# BOOSTXL-BATPAKMKII.net
KiCad netlist of a schematic drawn in EAGLE
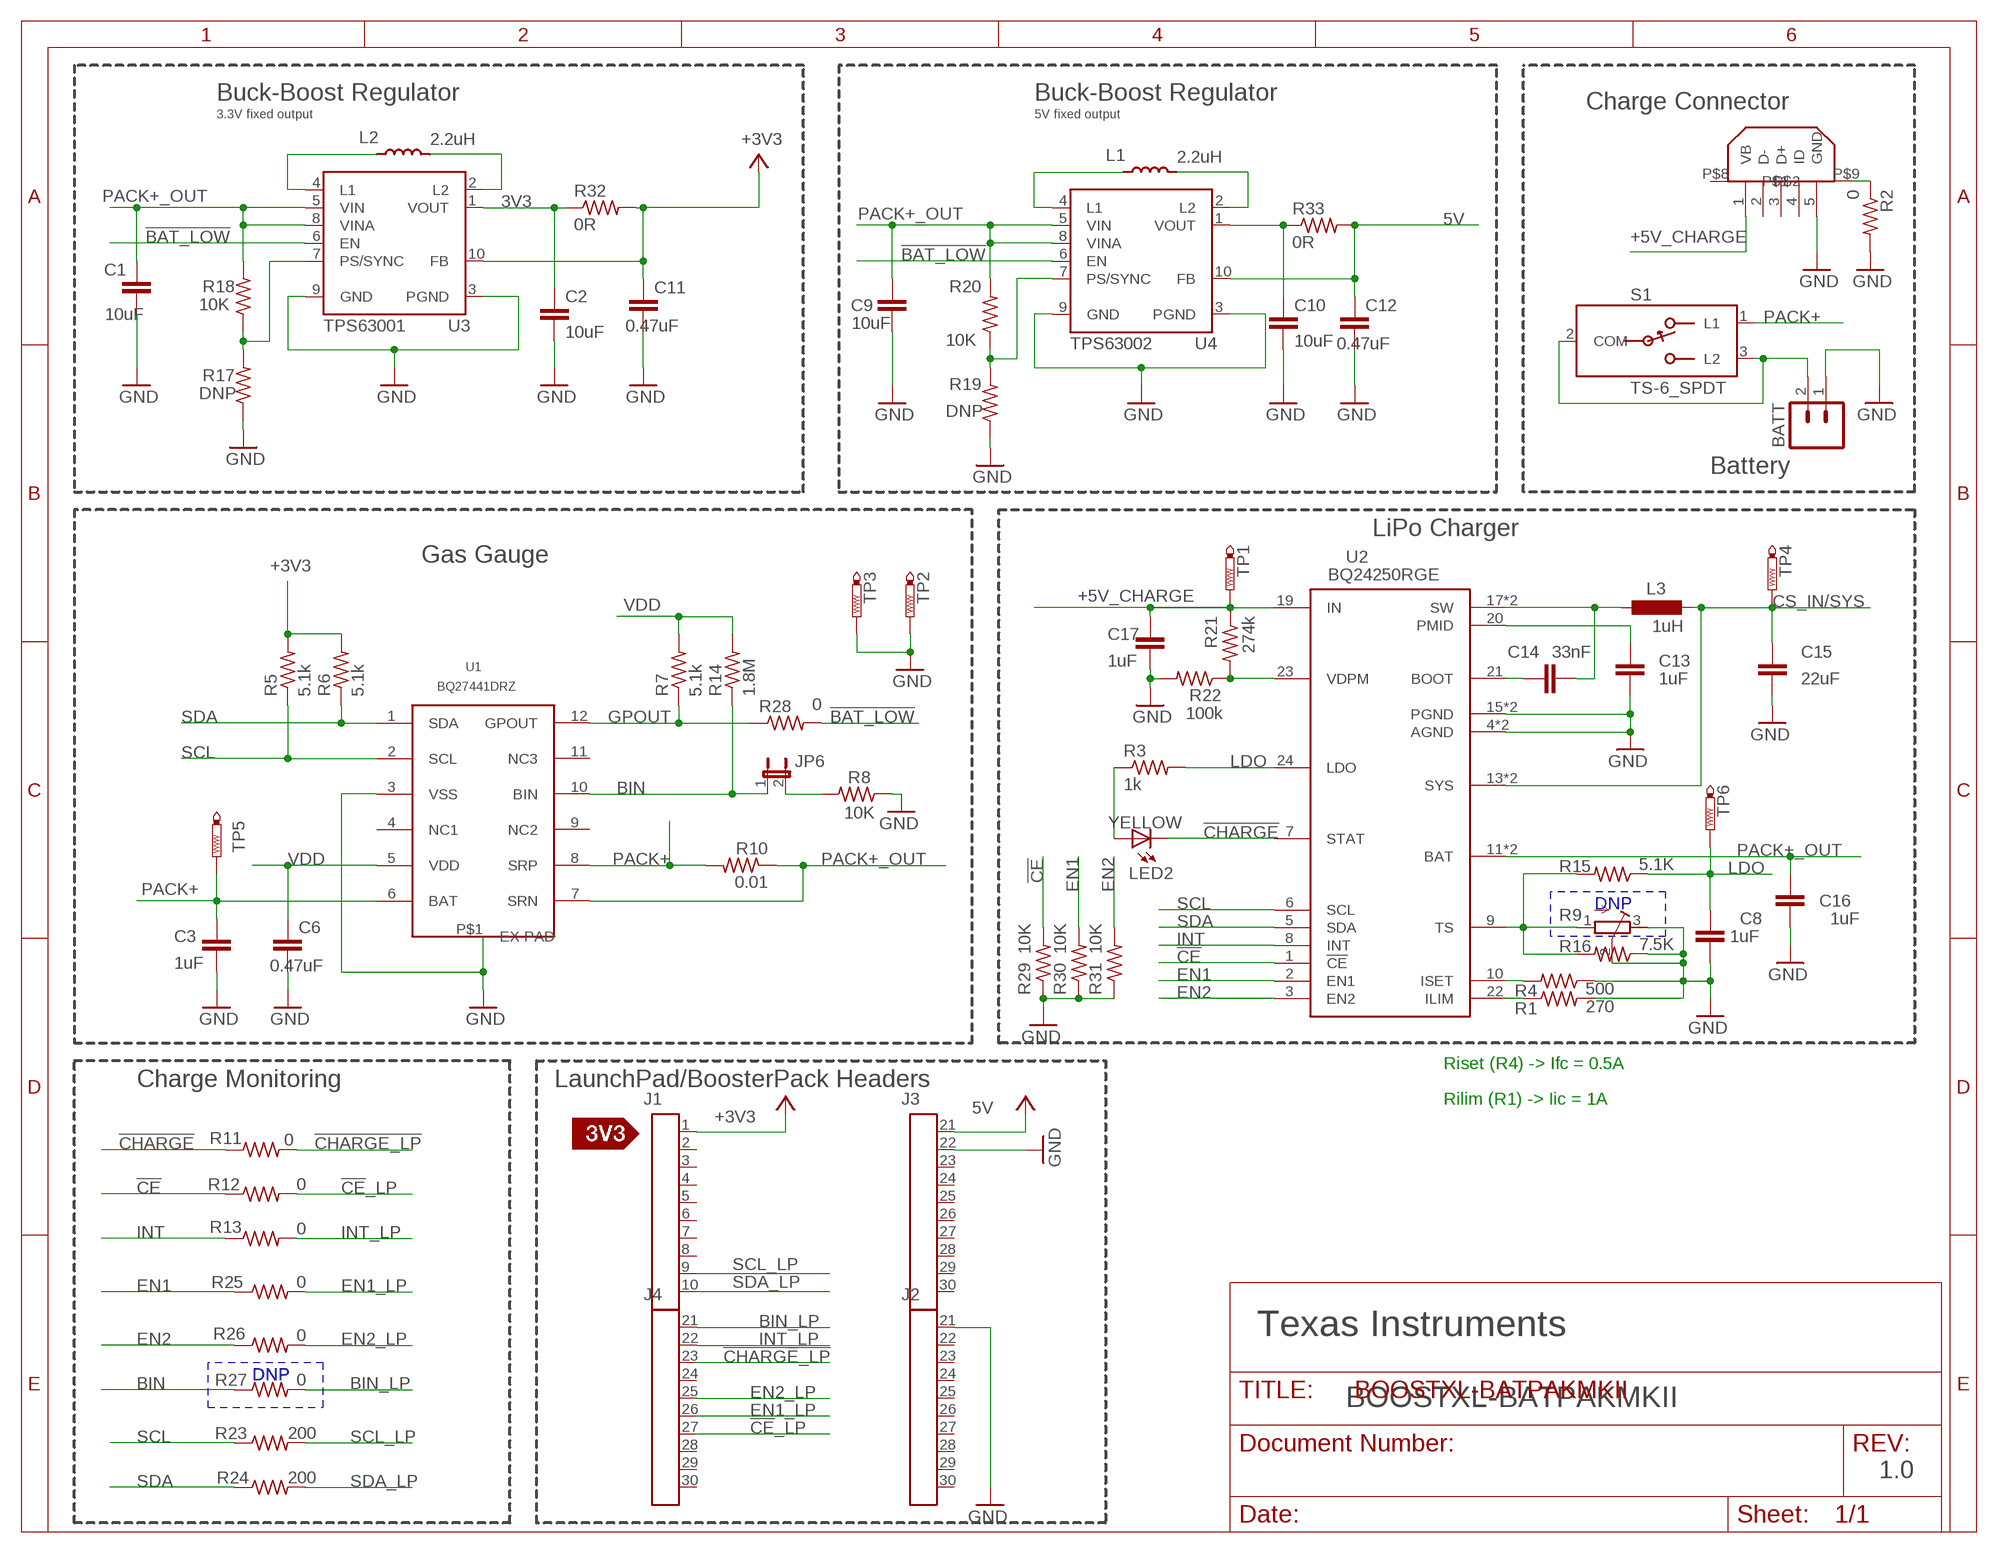
[diagram p0: schematic, sheet 1]

(export (version "E")
  (design (tool "Eeschema 10.0.6"))
  (components
    (comp (ref "BATT")
      (value "M02-JST-2MM-SMT")
      (footprint "eagle-import:JST-2-SMD")
      (libsource (lib "eagle-import") (part "M02-JST-2MM-SMT"))
    )
    (comp (ref "C1")
      (value "10uF")
      (footprint "eagle-import:C0603")
      (libsource (lib "eagle-import") (part "C-EUC0603"))
    )
    (comp (ref "C2")
      (value "10uF")
      (footprint "eagle-import:C0603")
      (libsource (lib "eagle-import") (part "C-EUC0603"))
    )
    (comp (ref "C3")
      (value "1uF")
      (footprint "eagle-import:C0603")
      (libsource (lib "eagle-import") (part "C-EUC0603"))
    )
    (comp (ref "C6")
      (value "0.47uF")
      (footprint "eagle-import:C0603")
      (libsource (lib "eagle-import") (part "C-EUC0603"))
    )
    (comp (ref "C8")
      (value "1uF")
      (footprint "eagle-import:C0603")
      (libsource (lib "eagle-import") (part "C-EUC0603"))
    )
    (comp (ref "C9")
      (value "10uF")
      (footprint "eagle-import:C0603")
      (libsource (lib "eagle-import") (part "C-EUC0603"))
    )
    (comp (ref "C10")
      (value "10uF")
      (footprint "eagle-import:C0603")
      (libsource (lib "eagle-import") (part "C-EUC0603"))
    )
    (comp (ref "C11")
      (value "0.47uF")
      (footprint "eagle-import:C0603")
      (libsource (lib "eagle-import") (part "C-EUC0603"))
    )
    (comp (ref "C12")
      (value "0.47uF")
      (footprint "eagle-import:C0603")
      (libsource (lib "eagle-import") (part "C-EUC0603"))
    )
    (comp (ref "C13")
      (value "1uF")
      (footprint "eagle-import:C0603")
      (libsource (lib "eagle-import") (part "C-EUC0603"))
    )
    (comp (ref "C14")
      (value "33nF")
      (footprint "eagle-import:C0603")
      (libsource (lib "eagle-import") (part "C-EUC0603"))
    )
    (comp (ref "C15")
      (value "22uF")
      (footprint "eagle-import:C0603")
      (libsource (lib "eagle-import") (part "C-EUC0603"))
    )
    (comp (ref "C16")
      (value "1uF")
      (footprint "eagle-import:C0603")
      (libsource (lib "eagle-import") (part "C-EUC0603"))
    )
    (comp (ref "C17")
      (value "1uF")
      (footprint "eagle-import:C0603")
      (libsource (lib "eagle-import") (part "C-EUC0603"))
    )
    (comp (ref "J1")
      (value "HEADER1X10")
      (footprint "eagle-import:1X10")
      (libsource (lib "eagle-import") (part "HEADER1X10"))
    )
    (comp (ref "J2")
      (value "HEADER1X10-J3")
      (footprint "eagle-import:1X10-J3")
      (libsource (lib "eagle-import") (part "HEADER1X10-J3"))
    )
    (comp (ref "J3")
      (value "HEADER1X10-J3")
      (footprint "eagle-import:1X10-J3")
      (libsource (lib "eagle-import") (part "HEADER1X10-J3"))
    )
    (comp (ref "J4")
      (value "HEADER1X10-J3")
      (footprint "eagle-import:1X10-J3")
      (libsource (lib "eagle-import") (part "HEADER1X10-J3"))
    )
    (comp (ref "JP6")
      (value "JP1E")
      (footprint "eagle-import:JP1")
      (libsource (lib "eagle-import") (part "JP1E"))
    )
    (comp (ref "L1")
      (value "2.2uH")
      (footprint "eagle-import:VLF4102A")
      (libsource (lib "eagle-import") (part "VLF4012A"))
    )
    (comp (ref "L2")
      (value "2.2uH")
      (footprint "eagle-import:VLF4102A")
      (libsource (lib "eagle-import") (part "VLF4012A"))
    )
    (comp (ref "L3")
      (value "1uH")
      (footprint "eagle-import:L3216C")
      (libsource (lib "eagle-import") (part "L-EUL3216C"))
    )
    (comp (ref "LED2")
      (value "YELLOW")
      (footprint "eagle-import:RIGHTANGLE_1208")
      (libsource (lib "eagle-import") (part "LED_1208"))
    )
    (comp (ref "R1")
      (value "270")
      (footprint "eagle-import:R0603")
      (libsource (lib "eagle-import") (part "R-US_R0603"))
    )
    (comp (ref "R2")
      (value "0")
      (footprint "eagle-import:R0603")
      (libsource (lib "eagle-import") (part "R-US_R0603"))
    )
    (comp (ref "R3")
      (value "1k")
      (footprint "eagle-import:R0603")
      (libsource (lib "eagle-import") (part "R-US_R0603"))
    )
    (comp (ref "R4")
      (value "500")
      (footprint "eagle-import:R0603")
      (libsource (lib "eagle-import") (part "R-US_R0603"))
    )
    (comp (ref "R5")
      (value "5.1k")
      (footprint "eagle-import:R0603")
      (libsource (lib "eagle-import") (part "R-US_R0603"))
    )
    (comp (ref "R6")
      (value "5.1k")
      (footprint "eagle-import:R0603")
      (libsource (lib "eagle-import") (part "R-US_R0603"))
    )
    (comp (ref "R7")
      (value "5.1k")
      (footprint "eagle-import:R0603")
      (libsource (lib "eagle-import") (part "R-US_R0603"))
    )
    (comp (ref "R8")
      (value "10K")
      (footprint "eagle-import:R0603")
      (libsource (lib "eagle-import") (part "R-US_R0603"))
    )
    (comp (ref "R9")
      (value "R-TRIMM3296W")
      (footprint "eagle-import:RTRIM3296W")
      (libsource (lib "eagle-import") (part "R-TRIMM3296W"))
    )
    (comp (ref "R10")
      (value "0.01")
      (footprint "eagle-import:R1206")
      (libsource (lib "eagle-import") (part "R-US_R1206"))
    )
    (comp (ref "R11")
      (value "0")
      (footprint "eagle-import:R0603")
      (libsource (lib "eagle-import") (part "R-US_R0603"))
    )
    (comp (ref "R12")
      (value "0")
      (footprint "eagle-import:R0603")
      (libsource (lib "eagle-import") (part "R-US_R0603"))
    )
    (comp (ref "R13")
      (value "0")
      (footprint "eagle-import:R0603")
      (libsource (lib "eagle-import") (part "R-US_R0603"))
    )
    (comp (ref "R14")
      (value "1.8M")
      (footprint "eagle-import:R0603")
      (libsource (lib "eagle-import") (part "R-US_R0603"))
    )
    (comp (ref "R15")
      (value "5.1K")
      (footprint "eagle-import:R0603")
      (libsource (lib "eagle-import") (part "R-US_R0603"))
    )
    (comp (ref "R16")
      (value "7.5K")
      (footprint "eagle-import:R0603")
      (libsource (lib "eagle-import") (part "R-US_R0603"))
    )
    (comp (ref "R17")
      (value "DNP")
      (footprint "eagle-import:R0603")
      (libsource (lib "eagle-import") (part "R-US_R0603"))
    )
    (comp (ref "R18")
      (value "10K")
      (footprint "eagle-import:R0603")
      (libsource (lib "eagle-import") (part "R-US_R0603"))
    )
    (comp (ref "R19")
      (value "DNP")
      (footprint "eagle-import:R0603")
      (libsource (lib "eagle-import") (part "R-US_R0603"))
    )
    (comp (ref "R20")
      (value "10K")
      (footprint "eagle-import:R0603")
      (libsource (lib "eagle-import") (part "R-US_R0603"))
    )
    (comp (ref "R21")
      (value "274k")
      (footprint "eagle-import:R0603")
      (libsource (lib "eagle-import") (part "R-US_R0603"))
    )
    (comp (ref "R22")
      (value "100k")
      (footprint "eagle-import:R0603")
      (libsource (lib "eagle-import") (part "R-US_R0603"))
    )
    (comp (ref "R23")
      (value "200")
      (footprint "eagle-import:R0603")
      (libsource (lib "eagle-import") (part "R-US_R0603"))
    )
    (comp (ref "R24")
      (value "200")
      (footprint "eagle-import:R0603")
      (libsource (lib "eagle-import") (part "R-US_R0603"))
    )
    (comp (ref "R25")
      (value "0")
      (footprint "eagle-import:R0603")
      (libsource (lib "eagle-import") (part "R-US_R0603"))
    )
    (comp (ref "R26")
      (value "0")
      (footprint "eagle-import:R0603")
      (libsource (lib "eagle-import") (part "R-US_R0603"))
    )
    (comp (ref "R27")
      (value "0")
      (footprint "eagle-import:R0603")
      (libsource (lib "eagle-import") (part "R-US_R0603"))
    )
    (comp (ref "R28")
      (value "0")
      (footprint "eagle-import:R0603")
      (libsource (lib "eagle-import") (part "R-US_R0603"))
    )
    (comp (ref "R29")
      (value "10K")
      (footprint "eagle-import:R0603")
      (libsource (lib "eagle-import") (part "R-US_R0603"))
    )
    (comp (ref "R30")
      (value "10K")
      (footprint "eagle-import:R0603")
      (libsource (lib "eagle-import") (part "R-US_R0603"))
    )
    (comp (ref "R31")
      (value "10K")
      (footprint "eagle-import:R0603")
      (libsource (lib "eagle-import") (part "R-US_R0603"))
    )
    (comp (ref "R32")
      (value "0R")
      (footprint "eagle-import:R0805")
      (libsource (lib "eagle-import") (part "R-US_R0805"))
    )
    (comp (ref "R33")
      (value "0R")
      (footprint "eagle-import:R0805")
      (libsource (lib "eagle-import") (part "R-US_R0805"))
    )
    (comp (ref "S1")
      (value "TS-6_SPDT")
      (footprint "eagle-import:TS-6_SPDT")
      (libsource (lib "eagle-import") (part "TS-6_SPDT"))
    )
    (comp (ref "TP1")
      (value "PTR1PAD1-13")
      (footprint "eagle-import:P1-13")
      (libsource (lib "eagle-import") (part "PTR1PAD1-13"))
    )
    (comp (ref "TP2")
      (value "PTR1PAD1-13")
      (footprint "eagle-import:P1-13")
      (libsource (lib "eagle-import") (part "PTR1PAD1-13"))
    )
    (comp (ref "TP3")
      (value "PTR1PAD1-13")
      (footprint "eagle-import:P1-13")
      (libsource (lib "eagle-import") (part "PTR1PAD1-13"))
    )
    (comp (ref "TP4")
      (value "PTR1PAD1-13")
      (footprint "eagle-import:P1-13")
      (libsource (lib "eagle-import") (part "PTR1PAD1-13"))
    )
    (comp (ref "TP5")
      (value "PTR1PAD1-13")
      (footprint "eagle-import:P1-13")
      (libsource (lib "eagle-import") (part "PTR1PAD1-13"))
    )
    (comp (ref "TP6")
      (value "PTR1PAD1-13")
      (footprint "eagle-import:P1-13")
      (libsource (lib "eagle-import") (part "PTR1PAD1-13"))
    )
    (comp (ref "U$1")
      (value "SILK_3V3_TAG")
      (footprint "eagle-import:SILK_3V3_TAG")
      (libsource (lib "eagle-import") (part "SILK_3V3_TAG"))
    )
    (comp (ref "U$2")
      (value "MS_(TM)")
      (footprint "eagle-import:MS_(TM)")
      (libsource (lib "eagle-import") (part "MS_(TM)"))
    )
    (comp (ref "U1")
      (value "BQ27441DRZ")
      (footprint "eagle-import:DRZ12")
      (libsource (lib "eagle-import") (part "BQ27441DRZ"))
    )
    (comp (ref "U2")
      (value "BQ24250RGE")
      (footprint "eagle-import:TI_RGE24")
      (libsource (lib "eagle-import") (part "BQ24250RGE"))
    )
    (comp (ref "U3")
      (value "TPS63001")
      (footprint "eagle-import:DRC-S-PVSON-N10")
      (fields (field (name "MPN") "TPS63000DRCTG4"))
      (libsource (lib "eagle-import") (part "TPS6300"))
    )
    (comp (ref "U4")
      (value "TPS63002")
      (footprint "eagle-import:DRC-S-PVSON-N10")
      (fields (field (name "MPN") "TPS63000DRCTG4"))
      (libsource (lib "eagle-import") (part "TPS6300"))
    )
    (comp (ref "USB")
      (value "CONN_USB_MICRO_B")
      (footprint "eagle-import:USB_MICRO_B_SMT")
      (libsource (lib "eagle-import") (part "CONN_USB_MICRO_B"))
    )
  )
  (nets
    (net (code "1") (name "+3V3") (class "Default")
      (node (ref "C11") (pin "1") (pinfunction "1_1") (pintype "passive"))
      (node (ref "J1") (pin "1") (pinfunction "1_1") (pintype "bidirectional"))
      (node (ref "R32") (pin "2") (pinfunction "2_2") (pintype "passive"))
      (node (ref "R5") (pin "2") (pinfunction "2_2") (pintype "passive"))
      (node (ref "R6") (pin "2") (pinfunction "2_2") (pintype "passive"))
      (node (ref "U3") (pin "10") (pinfunction "FB_10") (pintype "input"))
    )
    (net (code "2") (name "/+5V_CHARGE") (class "Default")
      (node (ref "C17") (pin "1") (pinfunction "1_1") (pintype "passive"))
      (node (ref "R21") (pin "1") (pinfunction "1_1") (pintype "passive"))
      (node (ref "TP1") (pin "TP") (pinfunction "TP_TP") (pintype "input"))
      (node (ref "U2") (pin "19") (pinfunction "IN_19") (pintype "bidirectional"))
      (node (ref "USB") (pin "1") (pinfunction "VB_1") (pintype "bidirectional"))
    )
    (net (code "3") (name "/3V3") (class "Default")
      (node (ref "C2") (pin "1") (pinfunction "1_1") (pintype "passive"))
      (node (ref "R32") (pin "1") (pinfunction "1_1") (pintype "passive"))
      (node (ref "U3") (pin "1") (pinfunction "VOUT_1") (pintype "output"))
    )
    (net (code "4") (name "/BIN") (class "Default")
      (node (ref "JP6") (pin "1") (pinfunction "1_1") (pintype "passive"))
      (node (ref "R14") (pin "1") (pinfunction "1_1") (pintype "passive"))
      (node (ref "R27") (pin "1") (pinfunction "1_1") (pintype "passive"))
      (node (ref "U1") (pin "10") (pinfunction "BIN_10") (pintype "bidirectional"))
    )
    (net (code "5") (name "/BIN_LP") (class "Default")
      (node (ref "J4") (pin "21") (pinfunction "1_21") (pintype "bidirectional"))
      (node (ref "R27") (pin "2") (pinfunction "2_2") (pintype "passive"))
    )
    (net (code "6") (name "/CS_IN{slash}SYS") (class "Default")
      (node (ref "C15") (pin "1") (pinfunction "1_1") (pintype "passive"))
      (node (ref "L3") (pin "2") (pinfunction "2_2") (pintype "passive"))
      (node (ref "TP4") (pin "TP") (pinfunction "TP_TP") (pintype "input"))
      (node (ref "U2") (pin "13") (pinfunction "SYS_13") (pintype "bidirectional"))
      (node (ref "U2") (pin "14") (pinfunction "SYS_14") (pintype "bidirectional"))
    )
    (net (code "7") (name "/EN1") (class "Default")
      (node (ref "R25") (pin "1") (pinfunction "1_1") (pintype "passive"))
      (node (ref "R30") (pin "2") (pinfunction "2_2") (pintype "passive"))
      (node (ref "U2") (pin "2") (pinfunction "EN1_2") (pintype "bidirectional"))
    )
    (net (code "8") (name "/EN1_LP") (class "Default")
      (node (ref "J4") (pin "26") (pinfunction "6_26") (pintype "bidirectional"))
      (node (ref "R25") (pin "2") (pinfunction "2_2") (pintype "passive"))
    )
    (net (code "9") (name "/EN2") (class "Default")
      (node (ref "R26") (pin "1") (pinfunction "1_1") (pintype "passive"))
      (node (ref "R31") (pin "2") (pinfunction "2_2") (pintype "passive"))
      (node (ref "U2") (pin "3") (pinfunction "EN2_3") (pintype "bidirectional"))
    )
    (net (code "10") (name "/EN2_LP") (class "Default")
      (node (ref "J4") (pin "25") (pinfunction "5_25") (pintype "bidirectional"))
      (node (ref "R26") (pin "2") (pinfunction "2_2") (pintype "passive"))
    )
    (net (code "11") (name "/GPOUT") (class "Default")
      (node (ref "R28") (pin "1") (pinfunction "1_1") (pintype "passive"))
      (node (ref "R7") (pin "1") (pinfunction "1_1") (pintype "passive"))
      (node (ref "U1") (pin "12") (pinfunction "GPOUT_12") (pintype "bidirectional"))
    )
    (net (code "12") (name "/INT") (class "Default")
      (node (ref "R13") (pin "1") (pinfunction "1_1") (pintype "passive"))
      (node (ref "U2") (pin "8") (pinfunction "INT_8") (pintype "bidirectional"))
    )
    (net (code "13") (name "/INT_LP") (class "Default")
      (node (ref "J4") (pin "22") (pinfunction "2_22") (pintype "bidirectional"))
      (node (ref "R13") (pin "2") (pinfunction "2_2") (pintype "passive"))
    )
    (net (code "14") (name "/LDO") (class "Default")
      (node (ref "C8") (pin "1") (pinfunction "1_1") (pintype "passive"))
      (node (ref "R15") (pin "1") (pinfunction "1_1") (pintype "passive"))
      (node (ref "R3") (pin "2") (pinfunction "2_2") (pintype "passive"))
      (node (ref "TP6") (pin "TP") (pinfunction "TP_TP") (pintype "input"))
      (node (ref "U2") (pin "24") (pinfunction "LDO_24") (pintype "bidirectional"))
    )
    (net (code "15") (name "/PACK+") (class "Default")
      (node (ref "C3") (pin "1") (pinfunction "1_1") (pintype "passive"))
      (node (ref "R10") (pin "2") (pinfunction "2_2") (pintype "passive"))
      (node (ref "S1") (pin "1") (pinfunction "L1_1") (pintype "bidirectional"))
      (node (ref "TP5") (pin "TP") (pinfunction "TP_TP") (pintype "input"))
      (node (ref "U1") (pin "6") (pinfunction "BAT_6") (pintype "bidirectional"))
      (node (ref "U1") (pin "8") (pinfunction "SRP_8") (pintype "bidirectional"))
    )
    (net (code "16") (name "/PACK+_OUT") (class "Default")
      (node (ref "C1") (pin "1") (pinfunction "1_1") (pintype "passive"))
      (node (ref "C16") (pin "1") (pinfunction "1_1") (pintype "passive"))
      (node (ref "C9") (pin "1") (pinfunction "1_1") (pintype "passive"))
      (node (ref "R10") (pin "1") (pinfunction "1_1") (pintype "passive"))
      (node (ref "R18") (pin "2") (pinfunction "2_2") (pintype "passive"))
      (node (ref "R20") (pin "2") (pinfunction "2_2") (pintype "passive"))
      (node (ref "U1") (pin "7") (pinfunction "SRN_7") (pintype "bidirectional"))
      (node (ref "U2") (pin "11") (pinfunction "BAT_11") (pintype "bidirectional"))
      (node (ref "U2") (pin "12") (pinfunction "BAT_12") (pintype "bidirectional"))
      (node (ref "U3") (pin "5") (pinfunction "VIN_5") (pintype "input"))
      (node (ref "U3") (pin "8") (pinfunction "VINA_8") (pintype "input"))
      (node (ref "U4") (pin "5") (pinfunction "VIN_5") (pintype "input"))
      (node (ref "U4") (pin "8") (pinfunction "VINA_8") (pintype "input"))
    )
    (net (code "17") (name "/SCL") (class "Default")
      (node (ref "R23") (pin "1") (pinfunction "1_1") (pintype "passive"))
      (node (ref "R5") (pin "1") (pinfunction "1_1") (pintype "passive"))
      (node (ref "U1") (pin "2") (pinfunction "SCL_2") (pintype "bidirectional"))
      (node (ref "U2") (pin "6") (pinfunction "SCL_6") (pintype "bidirectional"))
    )
    (net (code "18") (name "/SCL_LP") (class "Default")
      (node (ref "J1") (pin "9") (pinfunction "9_9") (pintype "bidirectional"))
      (node (ref "R23") (pin "2") (pinfunction "2_2") (pintype "passive"))
    )
    (net (code "19") (name "/SDA") (class "Default")
      (node (ref "R24") (pin "1") (pinfunction "1_1") (pintype "passive"))
      (node (ref "R6") (pin "1") (pinfunction "1_1") (pintype "passive"))
      (node (ref "U1") (pin "1") (pinfunction "SDA_1") (pintype "bidirectional"))
      (node (ref "U2") (pin "5") (pinfunction "SDA_5") (pintype "bidirectional"))
    )
    (net (code "20") (name "/SDA_LP") (class "Default")
      (node (ref "J1") (pin "10") (pinfunction "10_10") (pintype "bidirectional"))
      (node (ref "R24") (pin "2") (pinfunction "2_2") (pintype "passive"))
    )
    (net (code "21") (name "/VDD") (class "Default")
      (node (ref "C6") (pin "1") (pinfunction "1_1") (pintype "passive"))
      (node (ref "R14") (pin "2") (pinfunction "2_2") (pintype "passive"))
      (node (ref "R7") (pin "2") (pinfunction "2_2") (pintype "passive"))
      (node (ref "U1") (pin "5") (pinfunction "VDD_5") (pintype "bidirectional"))
    )
    (net (code "22") (name "/~{BAT_LOW}") (class "Default")
      (node (ref "R28") (pin "2") (pinfunction "2_2") (pintype "passive"))
      (node (ref "U3") (pin "6") (pinfunction "EN_6") (pintype "input"))
      (node (ref "U4") (pin "6") (pinfunction "EN_6") (pintype "input"))
    )
    (net (code "23") (name "/~{CE}") (class "Default")
      (node (ref "R12") (pin "1") (pinfunction "1_1") (pintype "passive"))
      (node (ref "R29") (pin "2") (pinfunction "2_2") (pintype "passive"))
      (node (ref "U2") (pin "1") (pinfunction "~{CE}_1") (pintype "bidirectional"))
    )
    (net (code "24") (name "/~{CE}_LP") (class "Default")
      (node (ref "J4") (pin "27") (pinfunction "7_27") (pintype "bidirectional"))
      (node (ref "R12") (pin "2") (pinfunction "2_2") (pintype "passive"))
    )
    (net (code "25") (name "/~{CHARGE_LP}") (class "Default")
      (node (ref "J4") (pin "23") (pinfunction "3_23") (pintype "bidirectional"))
      (node (ref "R11") (pin "2") (pinfunction "2_2") (pintype "passive"))
    )
    (net (code "26") (name "/~{CHARGE}") (class "Default")
      (node (ref "LED2") (pin "CATHODE") (pinfunction "C_CATHODE") (pintype "passive"))
      (node (ref "R11") (pin "1") (pinfunction "1_1") (pintype "passive"))
      (node (ref "U2") (pin "7") (pinfunction "STAT_7") (pintype "bidirectional"))
    )
    (net (code "27") (name "5V") (class "Default")
      (node (ref "C12") (pin "1") (pinfunction "1_1") (pintype "passive"))
      (node (ref "J3") (pin "21") (pinfunction "1_21") (pintype "bidirectional"))
      (node (ref "R33") (pin "2") (pinfunction "2_2") (pintype "passive"))
      (node (ref "U4") (pin "10") (pinfunction "FB_10") (pintype "input"))
    )
    (net (code "28") (name "GND") (class "Default")
      (node (ref "BATT") (pin "1") (pinfunction "1_1") (pintype "passive"))
      (node (ref "C1") (pin "2") (pinfunction "2_2") (pintype "passive"))
      (node (ref "C10") (pin "2") (pinfunction "2_2") (pintype "passive"))
      (node (ref "C11") (pin "2") (pinfunction "2_2") (pintype "passive"))
      (node (ref "C12") (pin "2") (pinfunction "2_2") (pintype "passive"))
      (node (ref "C13") (pin "2") (pinfunction "2_2") (pintype "passive"))
      (node (ref "C15") (pin "2") (pinfunction "2_2") (pintype "passive"))
      (node (ref "C16") (pin "2") (pinfunction "2_2") (pintype "passive"))
      (node (ref "C17") (pin "2") (pinfunction "2_2") (pintype "passive"))
      (node (ref "C2") (pin "2") (pinfunction "2_2") (pintype "passive"))
      (node (ref "C3") (pin "2") (pinfunction "2_2") (pintype "passive"))
      (node (ref "C6") (pin "2") (pinfunction "2_2") (pintype "passive"))
      (node (ref "C8") (pin "2") (pinfunction "2_2") (pintype "passive"))
      (node (ref "C9") (pin "2") (pinfunction "2_2") (pintype "passive"))
      (node (ref "J2") (pin "21") (pinfunction "1_21") (pintype "bidirectional"))
      (node (ref "J3") (pin "22") (pinfunction "2_22") (pintype "bidirectional"))
      (node (ref "R1") (pin "2") (pinfunction "2_2") (pintype "passive"))
      (node (ref "R16") (pin "1") (pinfunction "1_1") (pintype "passive"))
      (node (ref "R17") (pin "1") (pinfunction "1_1") (pintype "passive"))
      (node (ref "R19") (pin "1") (pinfunction "1_1") (pintype "passive"))
      (node (ref "R2") (pin "2") (pinfunction "2_2") (pintype "passive"))
      (node (ref "R22") (pin "2") (pinfunction "2_2") (pintype "passive"))
      (node (ref "R29") (pin "1") (pinfunction "1_1") (pintype "passive"))
      (node (ref "R30") (pin "1") (pinfunction "1_1") (pintype "passive"))
      (node (ref "R31") (pin "1") (pinfunction "1_1") (pintype "passive"))
      (node (ref "R4") (pin "1") (pinfunction "1_1") (pintype "passive"))
      (node (ref "R8") (pin "1") (pinfunction "1_1") (pintype "passive"))
      (node (ref "R9") (pin "2") (pinfunction "S_2") (pintype "passive"))
      (node (ref "R9") (pin "3") (pinfunction "A_3") (pintype "passive"))
      (node (ref "TP2") (pin "TP") (pinfunction "TP_TP") (pintype "input"))
      (node (ref "TP3") (pin "TP") (pinfunction "TP_TP") (pintype "input"))
      (node (ref "U1") (pin "3") (pinfunction "VSS_3") (pintype "bidirectional"))
      (node (ref "U1") (pin "P$1") (pinfunction "EX-PAD_P$1") (pintype "bidirectional"))
      (node (ref "U2") (pin "15") (pinfunction "PGND_15") (pintype "bidirectional"))
      (node (ref "U2") (pin "16") (pinfunction "PGND_16") (pintype "bidirectional"))
      (node (ref "U2") (pin "4") (pinfunction "AGND_4") (pintype "bidirectional"))
      (node (ref "U2") (pin "P$1") (pinfunction "AGND_P$1") (pintype "bidirectional"))
      (node (ref "U3") (pin "3") (pinfunction "PGND_3") (pintype "power_in"))
      (node (ref "U3") (pin "9") (pinfunction "GND_9") (pintype "power_in"))
      (node (ref "U4") (pin "3") (pinfunction "PGND_3") (pintype "power_in"))
      (node (ref "U4") (pin "9") (pinfunction "GND_9") (pintype "power_in"))
      (node (ref "USB") (pin "5") (pinfunction "GND_5") (pintype "bidirectional"))
    )
    (net (code "29") (name "Net-(C14-Pad2)") (class "Default")
      (node (ref "C14") (pin "2") (pinfunction "2_2") (pintype "passive"))
      (node (ref "L3") (pin "1") (pinfunction "1_1") (pintype "passive"))
      (node (ref "U2") (pin "17") (pinfunction "SW_17") (pintype "bidirectional"))
      (node (ref "U2") (pin "18") (pinfunction "SW_18") (pintype "bidirectional"))
    )
    (net (code "30") (name "Net-(JP6-Pad2)") (class "Default")
      (node (ref "JP6") (pin "2") (pinfunction "2_2") (pintype "passive"))
      (node (ref "R8") (pin "2") (pinfunction "2_2") (pintype "passive"))
    )
    (net (code "31") (name "Net-(L1-P$2)") (class "Default")
      (node (ref "L1") (pin "P$3") (pinfunction "P$2_P$3") (pintype "bidirectional"))
      (node (ref "U4") (pin "4") (pinfunction "L1_4") (pintype "passive"))
    )
    (net (code "32") (name "Net-(L2-P$2)") (class "Default")
      (node (ref "L2") (pin "P$3") (pinfunction "P$2_P$3") (pintype "bidirectional"))
      (node (ref "U3") (pin "4") (pinfunction "L1_4") (pintype "passive"))
    )
    (net (code "33") (name "Net-(LED2-A)") (class "Default")
      (node (ref "LED2") (pin "ANODE") (pinfunction "A_ANODE") (pintype "passive"))
      (node (ref "R3") (pin "1") (pinfunction "1_1") (pintype "passive"))
    )
    (net (code "34") (name "Net-(R9-E)") (class "Default")
      (node (ref "R15") (pin "2") (pinfunction "2_2") (pintype "passive"))
      (node (ref "R16") (pin "2") (pinfunction "2_2") (pintype "passive"))
      (node (ref "R9") (pin "1") (pinfunction "E_1") (pintype "passive"))
      (node (ref "U2") (pin "9") (pinfunction "TS_9") (pintype "bidirectional"))
    )
    (net (code "35") (name "Net-(S1-COM)") (class "Default")
      (node (ref "BATT") (pin "2") (pinfunction "2_2") (pintype "passive"))
      (node (ref "S1") (pin "2") (pinfunction "COM_2") (pintype "bidirectional"))
      (node (ref "S1") (pin "3") (pinfunction "L2_3") (pintype "bidirectional"))
    )
    (net (code "36") (name "Net-(U2-BOOT)") (class "Default")
      (node (ref "C14") (pin "1") (pinfunction "1_1") (pintype "passive"))
      (node (ref "U2") (pin "21") (pinfunction "BOOT_21") (pintype "bidirectional"))
    )
    (net (code "37") (name "Net-(U2-ILIM)") (class "Default")
      (node (ref "R1") (pin "1") (pinfunction "1_1") (pintype "passive"))
      (node (ref "U2") (pin "22") (pinfunction "ILIM_22") (pintype "bidirectional"))
    )
    (net (code "38") (name "Net-(U2-ISET)") (class "Default")
      (node (ref "R4") (pin "2") (pinfunction "2_2") (pintype "passive"))
      (node (ref "U2") (pin "10") (pinfunction "ISET_10") (pintype "bidirectional"))
    )
    (net (code "39") (name "Net-(U2-PMID)") (class "Default")
      (node (ref "C13") (pin "1") (pinfunction "1_1") (pintype "passive"))
      (node (ref "U2") (pin "20") (pinfunction "PMID_20") (pintype "bidirectional"))
    )
    (net (code "40") (name "Net-(U2-VDPM)") (class "Default")
      (node (ref "R21") (pin "2") (pinfunction "2_2") (pintype "passive"))
      (node (ref "R22") (pin "1") (pinfunction "1_1") (pintype "passive"))
      (node (ref "U2") (pin "23") (pinfunction "VDPM_23") (pintype "bidirectional"))
    )
    (net (code "41") (name "Net-(U3A-L2)") (class "Default")
      (node (ref "L2") (pin "P$1") (pinfunction "P$1_P$1") (pintype "bidirectional"))
      (node (ref "U3") (pin "2") (pinfunction "L2_2") (pintype "passive"))
    )
    (net (code "42") (name "Net-(U3A-PS{slash}SYNC)") (class "Default")
      (node (ref "R17") (pin "2") (pinfunction "2_2") (pintype "passive"))
      (node (ref "R18") (pin "1") (pinfunction "1_1") (pintype "passive"))
      (node (ref "U3") (pin "7") (pinfunction "PS/SYNC_7") (pintype "input"))
    )
    (net (code "43") (name "Net-(U4A-L2)") (class "Default")
      (node (ref "L1") (pin "P$1") (pinfunction "P$1_P$1") (pintype "bidirectional"))
      (node (ref "U4") (pin "2") (pinfunction "L2_2") (pintype "passive"))
    )
    (net (code "44") (name "Net-(U4A-PS{slash}SYNC)") (class "Default")
      (node (ref "R19") (pin "2") (pinfunction "2_2") (pintype "passive"))
      (node (ref "R20") (pin "1") (pinfunction "1_1") (pintype "passive"))
      (node (ref "U4") (pin "7") (pinfunction "PS/SYNC_7") (pintype "input"))
    )
    (net (code "45") (name "Net-(U4A-VOUT)") (class "Default")
      (node (ref "C10") (pin "1") (pinfunction "1_1") (pintype "passive"))
      (node (ref "R33") (pin "1") (pinfunction "1_1") (pintype "passive"))
      (node (ref "U4") (pin "1") (pinfunction "VOUT_1") (pintype "output"))
    )
    (net (code "46") (name "Net-(USB-P$2)") (class "Default")
      (node (ref "R2") (pin "1") (pinfunction "1_1") (pintype "passive"))
      (node (ref "USB") (pin "P$9") (pinfunction "P$2_P$9") (pintype "bidirectional"))
    )
    (net (code "47") (name "unconnected-(J1-Pad2)") (class "Default")
      (node (ref "J1") (pin "2") (pinfunction "2_2") (pintype "bidirectional"))
    )
    (net (code "48") (name "unconnected-(J1-Pad3)") (class "Default")
      (node (ref "J1") (pin "3") (pinfunction "3_3") (pintype "bidirectional"))
    )
    (net (code "49") (name "unconnected-(J1-Pad4)") (class "Default")
      (node (ref "J1") (pin "4") (pinfunction "4_4") (pintype "bidirectional"))
    )
    (net (code "50") (name "unconnected-(J1-Pad5)") (class "Default")
      (node (ref "J1") (pin "5") (pinfunction "5_5") (pintype "bidirectional"))
    )
    (net (code "51") (name "unconnected-(J1-Pad6)") (class "Default")
      (node (ref "J1") (pin "6") (pinfunction "6_6") (pintype "bidirectional"))
    )
    (net (code "52") (name "unconnected-(J1-Pad7)") (class "Default")
      (node (ref "J1") (pin "7") (pinfunction "7_7") (pintype "bidirectional"))
    )
    (net (code "53") (name "unconnected-(J1-Pad8)") (class "Default")
      (node (ref "J1") (pin "8") (pinfunction "8_8") (pintype "bidirectional"))
    )
    (net (code "54") (name "unconnected-(J2-2-Pad22)") (class "Default")
      (node (ref "J2") (pin "22") (pinfunction "2_22") (pintype "bidirectional"))
    )
    (net (code "55") (name "unconnected-(J2-3-Pad23)") (class "Default")
      (node (ref "J2") (pin "23") (pinfunction "3_23") (pintype "bidirectional"))
    )
    (net (code "56") (name "unconnected-(J2-4-Pad24)") (class "Default")
      (node (ref "J2") (pin "24") (pinfunction "4_24") (pintype "bidirectional"))
    )
    (net (code "57") (name "unconnected-(J2-5-Pad25)") (class "Default")
      (node (ref "J2") (pin "25") (pinfunction "5_25") (pintype "bidirectional"))
    )
    (net (code "58") (name "unconnected-(J2-6-Pad26)") (class "Default")
      (node (ref "J2") (pin "26") (pinfunction "6_26") (pintype "bidirectional"))
    )
    (net (code "59") (name "unconnected-(J2-7-Pad27)") (class "Default")
      (node (ref "J2") (pin "27") (pinfunction "7_27") (pintype "bidirectional"))
    )
    (net (code "60") (name "unconnected-(J2-8-Pad28)") (class "Default")
      (node (ref "J2") (pin "28") (pinfunction "8_28") (pintype "bidirectional"))
    )
    (net (code "61") (name "unconnected-(J2-9-Pad29)") (class "Default")
      (node (ref "J2") (pin "29") (pinfunction "9_29") (pintype "bidirectional"))
    )
    (net (code "62") (name "unconnected-(J2-10-Pad30)") (class "Default")
      (node (ref "J2") (pin "30") (pinfunction "10_30") (pintype "bidirectional"))
    )
    (net (code "63") (name "unconnected-(J3-3-Pad23)") (class "Default")
      (node (ref "J3") (pin "23") (pinfunction "3_23") (pintype "bidirectional"))
    )
    (net (code "64") (name "unconnected-(J3-4-Pad24)") (class "Default")
      (node (ref "J3") (pin "24") (pinfunction "4_24") (pintype "bidirectional"))
    )
    (net (code "65") (name "unconnected-(J3-5-Pad25)") (class "Default")
      (node (ref "J3") (pin "25") (pinfunction "5_25") (pintype "bidirectional"))
    )
    (net (code "66") (name "unconnected-(J3-6-Pad26)") (class "Default")
      (node (ref "J3") (pin "26") (pinfunction "6_26") (pintype "bidirectional"))
    )
    (net (code "67") (name "unconnected-(J3-7-Pad27)") (class "Default")
      (node (ref "J3") (pin "27") (pinfunction "7_27") (pintype "bidirectional"))
    )
    (net (code "68") (name "unconnected-(J3-8-Pad28)") (class "Default")
      (node (ref "J3") (pin "28") (pinfunction "8_28") (pintype "bidirectional"))
    )
    (net (code "69") (name "unconnected-(J3-9-Pad29)") (class "Default")
      (node (ref "J3") (pin "29") (pinfunction "9_29") (pintype "bidirectional"))
    )
    (net (code "70") (name "unconnected-(J3-10-Pad30)") (class "Default")
      (node (ref "J3") (pin "30") (pinfunction "10_30") (pintype "bidirectional"))
    )
    (net (code "71") (name "unconnected-(J4-4-Pad24)") (class "Default")
      (node (ref "J4") (pin "24") (pinfunction "4_24") (pintype "bidirectional"))
    )
    (net (code "72") (name "unconnected-(J4-8-Pad28)") (class "Default")
      (node (ref "J4") (pin "28") (pinfunction "8_28") (pintype "bidirectional"))
    )
    (net (code "73") (name "unconnected-(J4-9-Pad29)") (class "Default")
      (node (ref "J4") (pin "29") (pinfunction "9_29") (pintype "bidirectional"))
    )
    (net (code "74") (name "unconnected-(J4-10-Pad30)") (class "Default")
      (node (ref "J4") (pin "30") (pinfunction "10_30") (pintype "bidirectional"))
    )
    (net (code "75") (name "unconnected-(U1-NC1-Pad4)") (class "Default")
      (node (ref "U1") (pin "4") (pinfunction "NC1_4") (pintype "bidirectional"))
    )
    (net (code "76") (name "unconnected-(U1-NC2-Pad9)") (class "Default")
      (node (ref "U1") (pin "9") (pinfunction "NC2_9") (pintype "bidirectional"))
    )
    (net (code "77") (name "unconnected-(U1-NC3-Pad11)") (class "Default")
      (node (ref "U1") (pin "11") (pinfunction "NC3_11") (pintype "bidirectional"))
    )
    (net (code "78") (name "unconnected-(USB-D+-Pad3)") (class "Default")
      (node (ref "USB") (pin "3") (pinfunction "D+_3") (pintype "bidirectional"))
    )
    (net (code "79") (name "unconnected-(USB-D--Pad2)") (class "Default")
      (node (ref "USB") (pin "2") (pinfunction "D-_2") (pintype "bidirectional"))
    )
    (net (code "80") (name "unconnected-(USB-ID-Pad4)") (class "Default")
      (node (ref "USB") (pin "4") (pinfunction "ID_4") (pintype "bidirectional"))
    )
    (net (code "81") (name "unconnected-(USB-P$1-PadP$8)") (class "Default")
      (node (ref "USB") (pin "P$8") (pinfunction "P$1_P$8") (pintype "bidirectional"))
    )
  )
)
